# ESP12F-SIMPLE-ACT4088.net
KiCad netlist of a schematic drawn in EAGLE
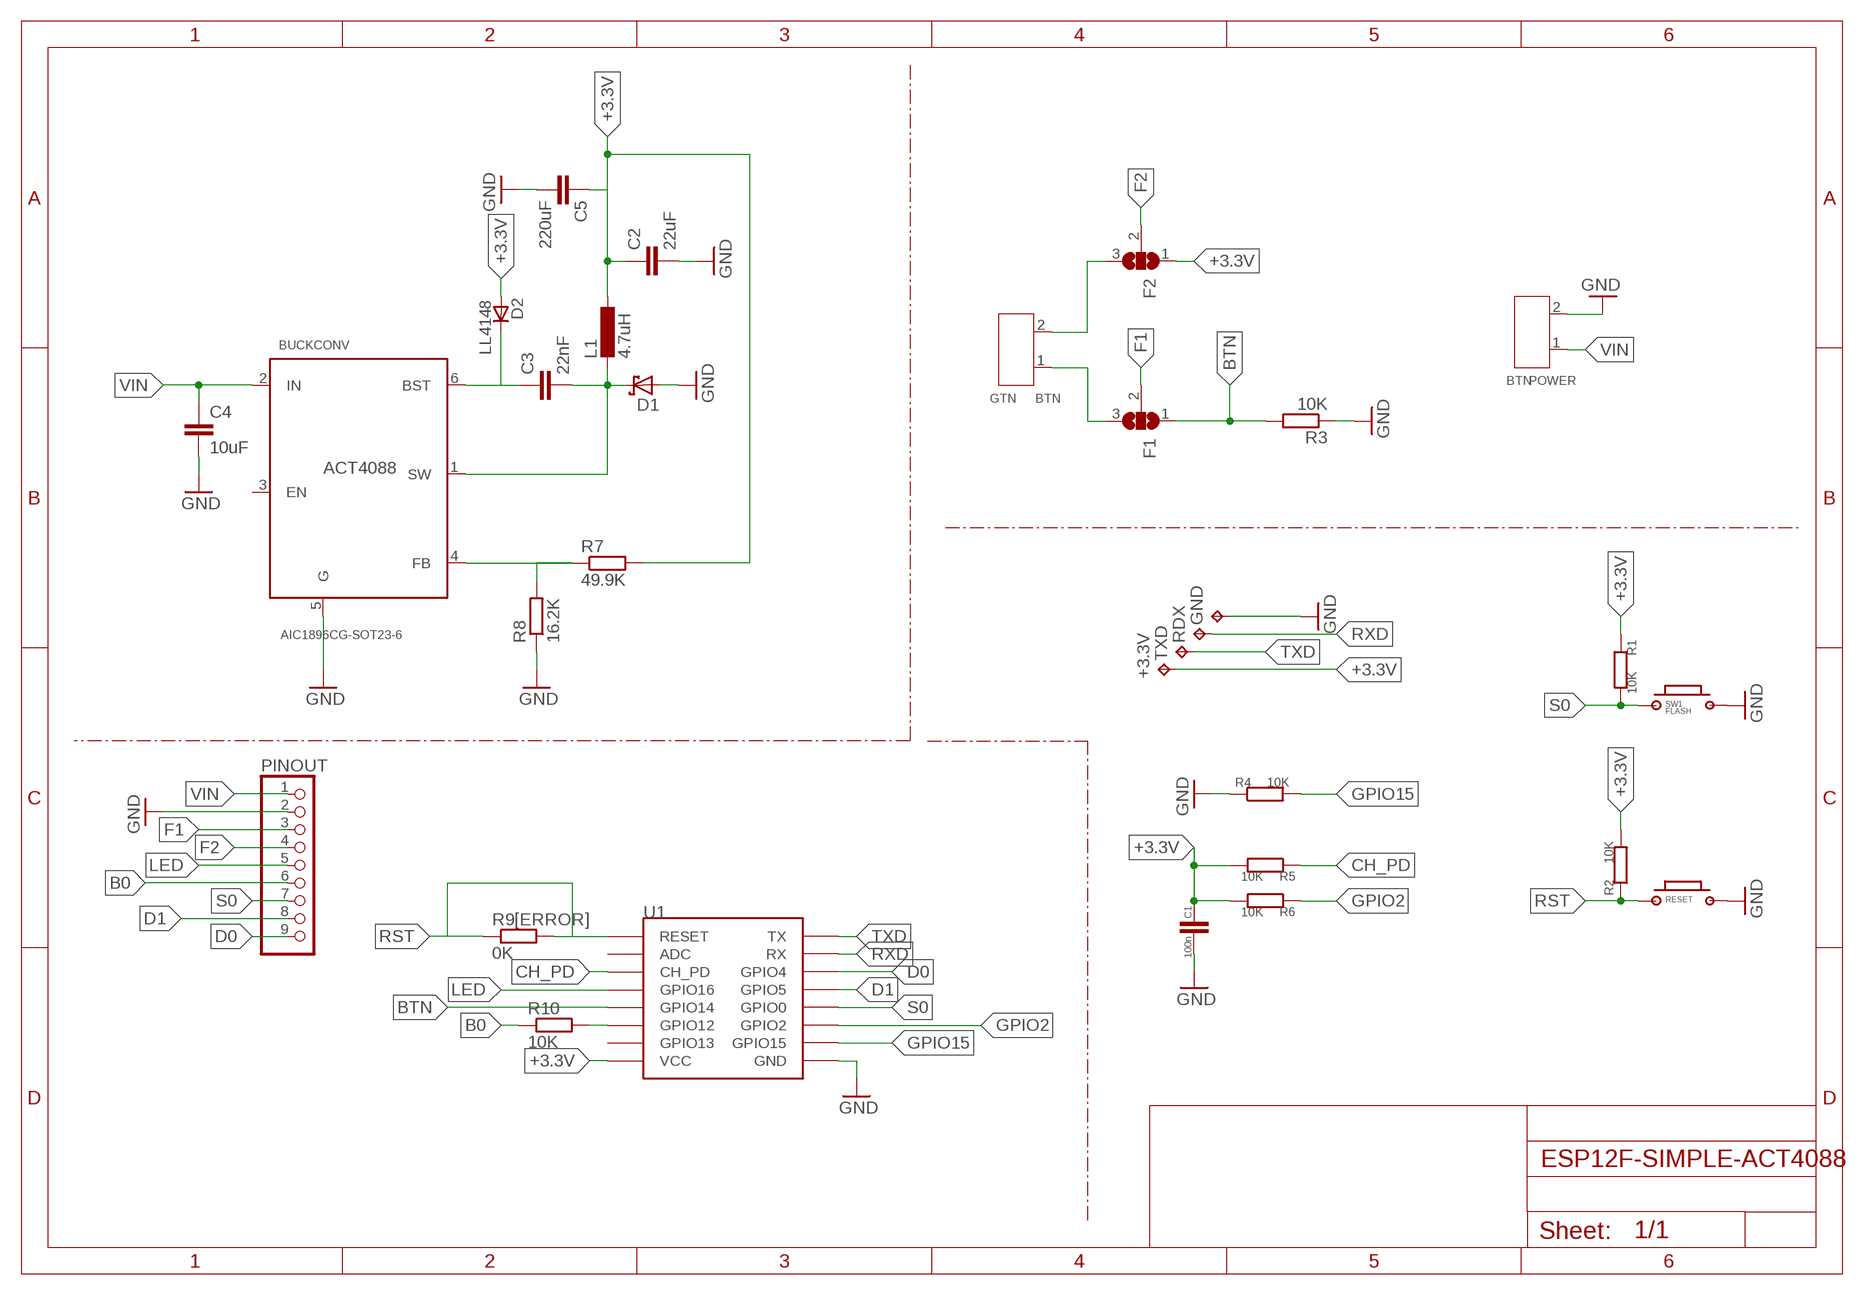
[diagram p0: schematic, sheet 1]

(export (version "E")
  (design (tool "Eeschema 10.0.6"))
  (components
    (comp (ref "+3.3V")
      (value "TPTP15R")
      (footprint "eagle-import:TP15R")
      (libsource (lib "eagle-import") (part "TPTP15R"))
    )
    (comp (ref "BTN")
      (value "GTN")
      (footprint "eagle-import:H2-3.5-7.0X7.0MM")
      (libsource (lib "eagle-import") (part "SCREW-TERMINAL-GREEN(2P-3.5)"))
    )
    (comp (ref "BUCKCONV")
      (value "AIC1896CG-SOT23-6")
      (footprint "eagle-import:SOT-23-6")
      (fields (field (name "MPN") "AIC1896CG"))
      (libsource (lib "eagle-import") (part "ACT4088-(SOT23-6)"))
    )
    (comp (ref "C1")
      (value "100n")
      (footprint "eagle-import:C_0805")
      (libsource (lib "eagle-import") (part "CAPC0805"))
    )
    (comp (ref "C2")
      (value "22uF")
      (footprint "eagle-import:C0805K")
      (libsource (lib "eagle-import") (part "C-EUC0805K"))
    )
    (comp (ref "C3")
      (value "22nF")
      (footprint "eagle-import:C0805K")
      (libsource (lib "eagle-import") (part "C-EUC0805K"))
    )
    (comp (ref "C4")
      (value "10uF")
      (footprint "eagle-import:C0805K")
      (libsource (lib "eagle-import") (part "C-EUC0805K"))
    )
    (comp (ref "C5")
      (value "220uF")
      (footprint "eagle-import:C1210")
      (libsource (lib "eagle-import") (part "resistor_C-EUC1210"))
    )
    (comp (ref "D1")
      (value "SCHOTTKY-DIODESMD")
      (footprint "eagle-import:SMB")
      (libsource (lib "eagle-import") (part "SCHOTTKY-DIODESMD"))
    )
    (comp (ref "D2")
      (value "LL4148")
      (footprint "eagle-import:SOD80_DO213AA_MINIMELF")
      (libsource (lib "eagle-import") (part "LL4148"))
    )
    (comp (ref "F1")
      (value "SJ2WX")
      (footprint "eagle-import:SJ_2XX")
      (libsource (lib "eagle-import") (part "SJ2WX"))
    )
    (comp (ref "F2")
      (value "SJ2WX")
      (footprint "eagle-import:SJ_2XX")
      (libsource (lib "eagle-import") (part "SJ2WX"))
    )
    (comp (ref "GND")
      (value "TPTP15R")
      (footprint "eagle-import:TP15R")
      (libsource (lib "eagle-import") (part "TPTP15R"))
    )
    (comp (ref "L1")
      (value "4.7uH")
      (footprint "eagle-import:L3225M")
      (libsource (lib "eagle-import") (part "L-EUL3225M"))
    )
    (comp (ref "PINOUT")
      (value "PINHD-1X9")
      (footprint "eagle-import:1X09")
      (libsource (lib "eagle-import") (part "PINHD-1X9"))
    )
    (comp (ref "POWER")
      (value "BTN")
      (footprint "eagle-import:H2-3.5-7.0X7.0MM")
      (libsource (lib "eagle-import") (part "SCREW-TERMINAL-GREEN(2P-3.5)"))
    )
    (comp (ref "R1")
      (value "10K")
      (footprint "eagle-import:R_0805")
      (libsource (lib "eagle-import") (part "RESISTORR0805"))
    )
    (comp (ref "R2")
      (value "10K")
      (footprint "eagle-import:R_0805")
      (libsource (lib "eagle-import") (part "RESISTORR0805"))
    )
    (comp (ref "R3")
      (value "10K")
      (footprint "eagle-import:R0805")
      (libsource (lib "eagle-import") (part "R-EU_R0805"))
    )
    (comp (ref "R4")
      (value "10K")
      (footprint "eagle-import:R_0805")
      (libsource (lib "eagle-import") (part "RESISTORR0805"))
    )
    (comp (ref "R5")
      (value "10K")
      (footprint "eagle-import:R_0805")
      (libsource (lib "eagle-import") (part "RESISTORR0805"))
    )
    (comp (ref "R6")
      (value "10K")
      (footprint "eagle-import:R_0805")
      (libsource (lib "eagle-import") (part "RESISTORR0805"))
    )
    (comp (ref "R7")
      (value "49.9K")
      (footprint "eagle-import:R0805")
      (libsource (lib "eagle-import") (part "R-EU_R0805"))
    )
    (comp (ref "R8")
      (value "16.2K")
      (footprint "eagle-import:R0805")
      (libsource (lib "eagle-import") (part "R-EU_R0805"))
    )
    (comp (ref "R9[ERROR]")
      (value "0K")
      (footprint "eagle-import:R0805")
      (libsource (lib "eagle-import") (part "R-EU_R0805"))
    )
    (comp (ref "R10")
      (value "10K")
      (footprint "eagle-import:R0805")
      (libsource (lib "eagle-import") (part "R-EU_R0805"))
    )
    (comp (ref "RDX")
      (value "TPTP15R")
      (footprint "eagle-import:TP15R")
      (libsource (lib "eagle-import") (part "TPTP15R"))
    )
    (comp (ref "RESET")
      (value "BUTTON-2PSWITCH-TURTLE-2P")
      (footprint "eagle-import:2P-SWITCH-TURTLE")
      (libsource (lib "eagle-import") (part "BUTTON-2PSWITCH-TURTLE-2P"))
    )
    (comp (ref "SW1")
      (value "FLASH")
      (footprint "eagle-import:2P-SWITCH-TURTLE")
      (libsource (lib "eagle-import") (part "BUTTON-2PSWITCH-TURTLE-2P"))
    )
    (comp (ref "TXD")
      (value "TPTP15R")
      (footprint "eagle-import:TP15R")
      (libsource (lib "eagle-import") (part "TPTP15R"))
    )
    (comp (ref "U1")
      (value "ESP12SMD")
      (footprint "eagle-import:ESP12-SMD")
      (libsource (lib "eagle-import") (part "ESP12SMD"))
    )
  )
  (nets
    (net (code "1") (name "+3.3V") (class "Default")
      (node (ref "+3.3V") (pin "TP") (pinfunction "TP_TP") (pintype "input"))
      (node (ref "C1") (pin "1") (pinfunction "1_1") (pintype "passive"))
      (node (ref "C2") (pin "1") (pinfunction "1_1") (pintype "passive"))
      (node (ref "C5") (pin "1") (pinfunction "1_1") (pintype "passive"))
      (node (ref "D2") (pin "A") (pinfunction "A_A") (pintype "passive"))
      (node (ref "F2") (pin "1") (pinfunction "1_1") (pintype "passive"))
      (node (ref "L1") (pin "1") (pinfunction "1_1") (pintype "passive"))
      (node (ref "R1") (pin "1") (pinfunction "1_1") (pintype "passive"))
      (node (ref "R2") (pin "2") (pinfunction "2_2") (pintype "passive"))
      (node (ref "R5") (pin "2") (pinfunction "2_2") (pintype "passive"))
      (node (ref "R6") (pin "2") (pinfunction "2_2") (pintype "passive"))
      (node (ref "R7") (pin "2") (pinfunction "2_2") (pintype "passive"))
      (node (ref "U1") (pin "VCC") (pinfunction "VCC_VCC") (pintype "bidirectional"))
    )
    (net (code "2") (name "B0") (class "Default")
      (node (ref "PINOUT") (pin "6") (pinfunction "6_6") (pintype "passive"))
      (node (ref "R10") (pin "1") (pinfunction "1_1") (pintype "passive"))
    )
    (net (code "3") (name "BTN") (class "Default")
      (node (ref "F1") (pin "1") (pinfunction "1_1") (pintype "passive"))
      (node (ref "R3") (pin "2") (pinfunction "2_2") (pintype "passive"))
      (node (ref "U1") (pin "GPIO14") (pinfunction "GPIO14_GPIO14") (pintype "bidirectional"))
    )
    (net (code "4") (name "CH_PD") (class "Default")
      (node (ref "R5") (pin "1") (pinfunction "1_1") (pintype "passive"))
      (node (ref "U1") (pin "CH_PD") (pinfunction "CH_PD_CH_PD") (pintype "bidirectional"))
    )
    (net (code "5") (name "D0") (class "Default")
      (node (ref "PINOUT") (pin "9") (pinfunction "9_9") (pintype "passive"))
      (node (ref "U1") (pin "GPIO4") (pinfunction "GPIO4_GPIO4") (pintype "bidirectional"))
    )
    (net (code "6") (name "D1") (class "Default")
      (node (ref "PINOUT") (pin "8") (pinfunction "8_8") (pintype "passive"))
      (node (ref "U1") (pin "GPIO5") (pinfunction "GPIO5_GPIO5") (pintype "bidirectional"))
    )
    (net (code "7") (name "F1") (class "Default")
      (node (ref "F1") (pin "2") (pinfunction "2_2") (pintype "passive"))
      (node (ref "PINOUT") (pin "3") (pinfunction "3_3") (pintype "passive"))
    )
    (net (code "8") (name "F2") (class "Default")
      (node (ref "F2") (pin "2") (pinfunction "2_2") (pintype "passive"))
      (node (ref "PINOUT") (pin "4") (pinfunction "4_4") (pintype "passive"))
    )
    (net (code "9") (name "GND") (class "Default")
      (node (ref "BUCKCONV") (pin "5") (pinfunction "G_5") (pintype "input"))
      (node (ref "C1") (pin "2") (pinfunction "2_2") (pintype "passive"))
      (node (ref "C2") (pin "2") (pinfunction "2_2") (pintype "passive"))
      (node (ref "C4") (pin "2") (pinfunction "2_2") (pintype "passive"))
      (node (ref "C5") (pin "2") (pinfunction "2_2") (pintype "passive"))
      (node (ref "D1") (pin "A") (pinfunction "A_A") (pintype "passive"))
      (node (ref "GND") (pin "TP") (pinfunction "TP_TP") (pintype "input"))
      (node (ref "PINOUT") (pin "2") (pinfunction "2_2") (pintype "passive"))
      (node (ref "POWER") (pin "2") (pinfunction "2_2") (pintype "bidirectional"))
      (node (ref "R3") (pin "1") (pinfunction "1_1") (pintype "passive"))
      (node (ref "R4") (pin "1") (pinfunction "1_1") (pintype "passive"))
      (node (ref "R8") (pin "1") (pinfunction "1_1") (pintype "passive"))
      (node (ref "RESET") (pin "2") (pinfunction "P$2_2") (pintype "bidirectional"))
      (node (ref "SW1") (pin "2") (pinfunction "P$2_2") (pintype "bidirectional"))
      (node (ref "U1") (pin "GND") (pinfunction "GND_GND") (pintype "bidirectional"))
    )
    (net (code "10") (name "GPIO2") (class "Default")
      (node (ref "R6") (pin "1") (pinfunction "1_1") (pintype "passive"))
      (node (ref "U1") (pin "GPIO2") (pinfunction "GPIO2_GPIO2") (pintype "bidirectional"))
    )
    (net (code "11") (name "GPIO15") (class "Default")
      (node (ref "R4") (pin "2") (pinfunction "2_2") (pintype "passive"))
      (node (ref "U1") (pin "GPIO15") (pinfunction "GPIO15_GPIO15") (pintype "bidirectional"))
    )
    (net (code "12") (name "LED") (class "Default")
      (node (ref "PINOUT") (pin "5") (pinfunction "5_5") (pintype "passive"))
      (node (ref "U1") (pin "GPIO16") (pinfunction "GPIO16_GPIO16") (pintype "bidirectional"))
    )
    (net (code "13") (name "Net-(BTN-Pad1)") (class "Default")
      (node (ref "BTN") (pin "1") (pinfunction "1_1") (pintype "bidirectional"))
      (node (ref "F1") (pin "3") (pinfunction "3_3") (pintype "passive"))
    )
    (net (code "14") (name "Net-(BTN-Pad2)") (class "Default")
      (node (ref "BTN") (pin "2") (pinfunction "2_2") (pintype "bidirectional"))
      (node (ref "F2") (pin "3") (pinfunction "3_3") (pintype "passive"))
    )
    (net (code "15") (name "Net-(BUCKCONV-BST)") (class "Default")
      (node (ref "BUCKCONV") (pin "6") (pinfunction "BST_6") (pintype "output"))
      (node (ref "C3") (pin "1") (pinfunction "1_1") (pintype "passive"))
      (node (ref "D2") (pin "C") (pinfunction "C_C") (pintype "passive"))
    )
    (net (code "16") (name "Net-(BUCKCONV-FB)") (class "Default")
      (node (ref "BUCKCONV") (pin "4") (pinfunction "FB_4") (pintype "power_in"))
      (node (ref "R7") (pin "1") (pinfunction "1_1") (pintype "passive"))
      (node (ref "R8") (pin "2") (pinfunction "2_2") (pintype "passive"))
    )
    (net (code "17") (name "Net-(BUCKCONV-SW)") (class "Default")
      (node (ref "BUCKCONV") (pin "1") (pinfunction "SW_1") (pintype "input"))
      (node (ref "C3") (pin "2") (pinfunction "2_2") (pintype "passive"))
      (node (ref "D1") (pin "C") (pinfunction "C_C") (pintype "passive"))
      (node (ref "L1") (pin "2") (pinfunction "2_2") (pintype "passive"))
    )
    (net (code "18") (name "Net-(R10-Pad2)") (class "Default")
      (node (ref "R10") (pin "2") (pinfunction "2_2") (pintype "passive"))
      (node (ref "U1") (pin "GPIO12") (pinfunction "GPIO12_GPIO12") (pintype "bidirectional"))
    )
    (net (code "19") (name "RST") (class "Default")
      (node (ref "R2") (pin "1") (pinfunction "1_1") (pintype "passive"))
      (node (ref "R9[ERROR]") (pin "1") (pinfunction "1_1") (pintype "passive"))
      (node (ref "R9[ERROR]") (pin "2") (pinfunction "2_2") (pintype "passive"))
      (node (ref "RESET") (pin "1") (pinfunction "P$1_1") (pintype "bidirectional"))
      (node (ref "U1") (pin "RESET") (pinfunction "RESET_RESET") (pintype "bidirectional"))
    )
    (net (code "20") (name "RXD") (class "Default")
      (node (ref "RDX") (pin "TP") (pinfunction "TP_TP") (pintype "input"))
      (node (ref "U1") (pin "RXD0") (pinfunction "RX_RXD0") (pintype "bidirectional"))
    )
    (net (code "21") (name "S0") (class "Default")
      (node (ref "PINOUT") (pin "7") (pinfunction "7_7") (pintype "passive"))
      (node (ref "R1") (pin "2") (pinfunction "2_2") (pintype "passive"))
      (node (ref "SW1") (pin "1") (pinfunction "P$1_1") (pintype "bidirectional"))
      (node (ref "U1") (pin "GPIO0") (pinfunction "GPIO0_GPIO0") (pintype "bidirectional"))
    )
    (net (code "22") (name "TXD") (class "Default")
      (node (ref "TXD") (pin "TP") (pinfunction "TP_TP") (pintype "input"))
      (node (ref "U1") (pin "TXD0") (pinfunction "TX_TXD0") (pintype "bidirectional"))
    )
    (net (code "23") (name "VIN") (class "Default")
      (node (ref "BUCKCONV") (pin "2") (pinfunction "IN_2") (pintype "input"))
      (node (ref "C4") (pin "1") (pinfunction "1_1") (pintype "passive"))
      (node (ref "PINOUT") (pin "1") (pinfunction "1_1") (pintype "passive"))
      (node (ref "POWER") (pin "1") (pinfunction "1_1") (pintype "bidirectional"))
    )
    (net (code "24") (name "unconnected-(BUCKCONV-EN-Pad3)") (class "Default")
      (node (ref "BUCKCONV") (pin "3") (pinfunction "EN_3") (pintype "input"))
    )
    (net (code "25") (name "unconnected-(U1-PadADC)") (class "Default")
      (node (ref "U1") (pin "ADC") (pinfunction "ADC_ADC") (pintype "bidirectional"))
    )
    (net (code "26") (name "unconnected-(U1-PadGPIO13)") (class "Default")
      (node (ref "U1") (pin "GPIO13") (pinfunction "GPIO13_GPIO13") (pintype "bidirectional"))
    )
  )
)
